# LEDdriverSFE_CREE.net
KiCad netlist of a schematic drawn in EAGLE
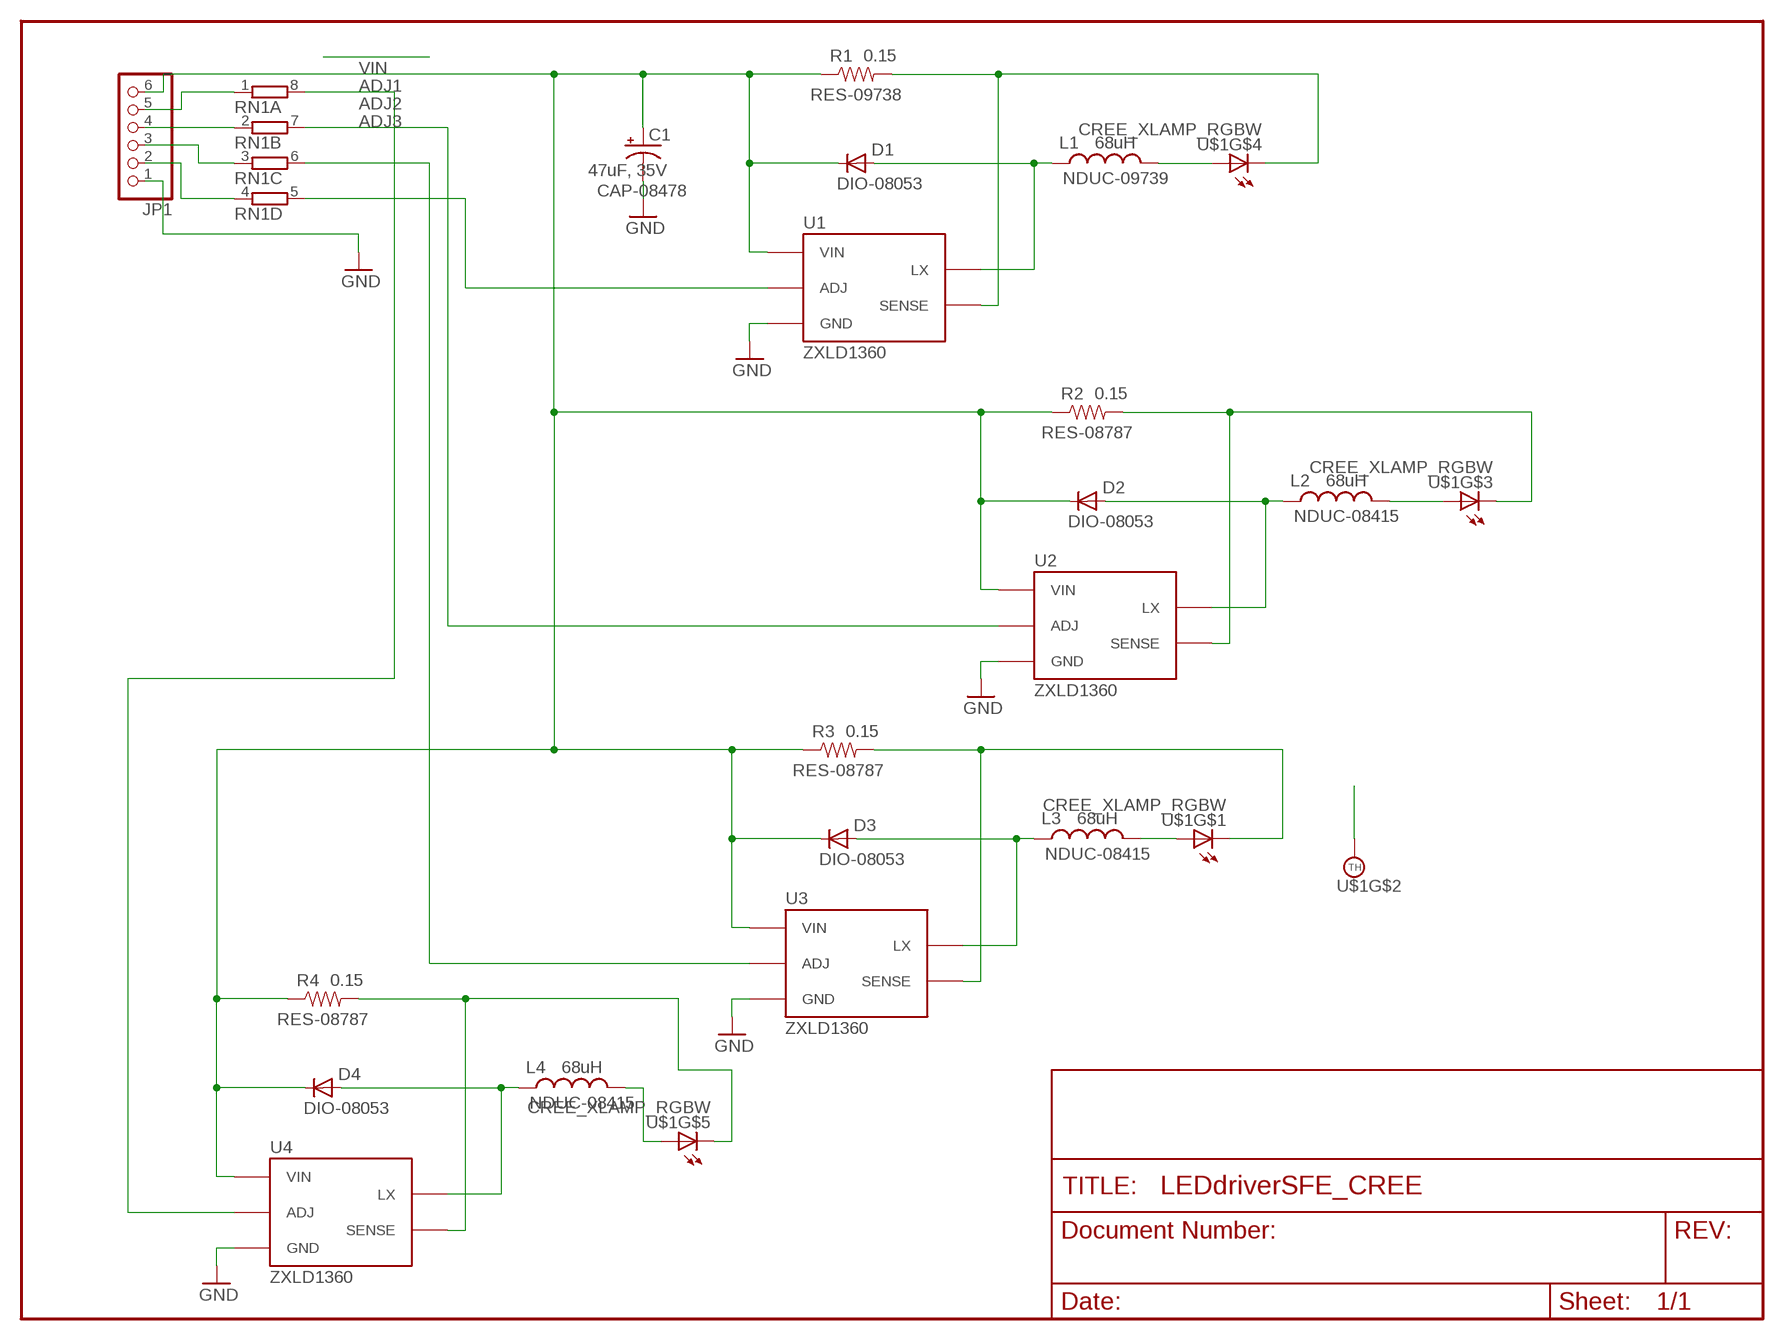
[diagram p0: schematic, sheet 1]

(export (version "E")
  (design (tool "Eeschema 10.0.6"))
  (components
    (comp (ref "C1")
      (value "47uF, 35V")
      (footprint "eagle-import:PANASONIC_D")
      (libsource (lib "eagle-import") (part "CAP_POLD"))
    )
    (comp (ref "D1")
      (value "MBRA140")
      (footprint "eagle-import:SMA-DIODE")
      (libsource (lib "eagle-import") (part "DIODESMA"))
    )
    (comp (ref "D2")
      (value "MBRA140")
      (footprint "eagle-import:SMA-DIODE")
      (libsource (lib "eagle-import") (part "DIODESMA"))
    )
    (comp (ref "D3")
      (value "MBRA140")
      (footprint "eagle-import:SMA-DIODE")
      (libsource (lib "eagle-import") (part "DIODESMA"))
    )
    (comp (ref "D4")
      (value "MBRA140")
      (footprint "eagle-import:SMA-DIODE")
      (libsource (lib "eagle-import") (part "DIODESMA"))
    )
    (comp (ref "JP1")
      (value "PINHD-1X6")
      (footprint "eagle-import:1X06")
      (libsource (lib "eagle-import") (part "PINHD-1X6"))
    )
    (comp (ref "L1")
      (value "68uH")
      (footprint "eagle-import:CR75")
      (libsource (lib "eagle-import") (part "INDUCTORCR75"))
    )
    (comp (ref "L2")
      (value "68uH")
      (footprint "eagle-import:CR75")
      (libsource (lib "eagle-import") (part "INDUCTORCR75"))
    )
    (comp (ref "L3")
      (value "68uH")
      (footprint "eagle-import:CR75")
      (libsource (lib "eagle-import") (part "INDUCTORCR75"))
    )
    (comp (ref "L4")
      (value "68uH")
      (footprint "eagle-import:CR75")
      (libsource (lib "eagle-import") (part "INDUCTORCR75"))
    )
    (comp (ref "R1")
      (value "0.15")
      (footprint "eagle-import:0603-RES")
      (libsource (lib "eagle-import") (part "RESISTOR0603-RES"))
    )
    (comp (ref "R2")
      (value "0.15")
      (footprint "eagle-import:0603-RES")
      (libsource (lib "eagle-import") (part "RESISTOR0603-RES"))
    )
    (comp (ref "R3")
      (value "0.15")
      (footprint "eagle-import:0603-RES")
      (libsource (lib "eagle-import") (part "RESISTOR0603-RES"))
    )
    (comp (ref "R4")
      (value "0.15")
      (footprint "eagle-import:0603-RES")
      (libsource (lib "eagle-import") (part "RESISTOR0603-RES"))
    )
    (comp (ref "RN1")
      (value "4R-NEXBV8V")
      (footprint "eagle-import:EXBV8V")
      (libsource (lib "eagle-import") (part "4R-NEXBV8V"))
    )
    (comp (ref "U$1")
      (value "CREE_XLAMP_RGBW")
      (footprint "eagle-import:CREE_XLAMP_XML")
      (libsource (lib "eagle-import") (part "CREE_XLAMP_RGBW"))
    )
    (comp (ref "U1")
      (value "ZXLD1360")
      (footprint "eagle-import:SOT23-5")
      (libsource (lib "eagle-import") (part "ZXLD1360"))
    )
    (comp (ref "U2")
      (value "ZXLD1360")
      (footprint "eagle-import:SOT23-5")
      (libsource (lib "eagle-import") (part "ZXLD1360"))
    )
    (comp (ref "U3")
      (value "ZXLD1360")
      (footprint "eagle-import:SOT23-5")
      (libsource (lib "eagle-import") (part "ZXLD1360"))
    )
    (comp (ref "U4")
      (value "ZXLD1360")
      (footprint "eagle-import:SOT23-5")
      (libsource (lib "eagle-import") (part "ZXLD1360"))
    )
  )
  (nets
    (net (code "1") (name "/ADJ1") (class "Default")
      (node (ref "RN1") (pin "5") (pinfunction "2_5") (pintype "passive"))
      (node (ref "U1") (pin "3") (pinfunction "ADJ_3") (pintype "bidirectional"))
    )
    (net (code "2") (name "/ADJ2") (class "Default")
      (node (ref "RN1") (pin "7") (pinfunction "2_7") (pintype "passive"))
      (node (ref "U2") (pin "3") (pinfunction "ADJ_3") (pintype "bidirectional"))
    )
    (net (code "3") (name "/ADJ3") (class "Default")
      (node (ref "RN1") (pin "6") (pinfunction "2_6") (pintype "passive"))
      (node (ref "U3") (pin "3") (pinfunction "ADJ_3") (pintype "bidirectional"))
    )
    (net (code "4") (name "/VIN") (class "Default")
      (node (ref "C1") (pin "+") (pinfunction "+_+") (pintype "passive"))
      (node (ref "D1") (pin "C") (pinfunction "C_C") (pintype "passive"))
      (node (ref "D2") (pin "C") (pinfunction "C_C") (pintype "passive"))
      (node (ref "D3") (pin "C") (pinfunction "C_C") (pintype "passive"))
      (node (ref "D4") (pin "C") (pinfunction "C_C") (pintype "passive"))
      (node (ref "JP1") (pin "6") (pinfunction "6_6") (pintype "passive"))
      (node (ref "R1") (pin "1") (pinfunction "1_1") (pintype "passive"))
      (node (ref "R2") (pin "1") (pinfunction "1_1") (pintype "passive"))
      (node (ref "R3") (pin "1") (pinfunction "1_1") (pintype "passive"))
      (node (ref "R4") (pin "1") (pinfunction "1_1") (pintype "passive"))
      (node (ref "U1") (pin "5") (pinfunction "VIN_5") (pintype "bidirectional"))
      (node (ref "U2") (pin "5") (pinfunction "VIN_5") (pintype "bidirectional"))
      (node (ref "U3") (pin "5") (pinfunction "VIN_5") (pintype "bidirectional"))
      (node (ref "U4") (pin "5") (pinfunction "VIN_5") (pintype "bidirectional"))
    )
    (net (code "5") (name "GND") (class "Default")
      (node (ref "C1") (pin "-") (pinfunction "-_-") (pintype "passive"))
      (node (ref "JP1") (pin "1") (pinfunction "1_1") (pintype "passive"))
      (node (ref "U1") (pin "2") (pinfunction "GND_2") (pintype "bidirectional"))
      (node (ref "U2") (pin "2") (pinfunction "GND_2") (pintype "bidirectional"))
      (node (ref "U3") (pin "2") (pinfunction "GND_2") (pintype "bidirectional"))
      (node (ref "U4") (pin "2") (pinfunction "GND_2") (pintype "bidirectional"))
    )
    (net (code "6") (name "Net-(JP1-Pad5)") (class "Default")
      (node (ref "JP1") (pin "5") (pinfunction "5_5") (pintype "passive"))
      (node (ref "RN1") (pin "1") (pinfunction "1_1") (pintype "passive"))
    )
    (net (code "7") (name "Net-(L1-1)") (class "Default")
      (node (ref "D1") (pin "A") (pinfunction "A_A") (pintype "passive"))
      (node (ref "L1") (pin "P$1") (pinfunction "1_P$1") (pintype "passive"))
      (node (ref "U1") (pin "1") (pinfunction "LX_1") (pintype "bidirectional"))
    )
    (net (code "8") (name "Net-(L1-2)") (class "Default")
      (node (ref "L1") (pin "P$2") (pinfunction "2_P$2") (pintype "passive"))
      (node (ref "U$1") (pin "3") (pinfunction "A_3") (pintype "passive"))
    )
    (net (code "9") (name "Net-(L2-1)") (class "Default")
      (node (ref "D2") (pin "A") (pinfunction "A_A") (pintype "passive"))
      (node (ref "L2") (pin "P$1") (pinfunction "1_P$1") (pintype "passive"))
      (node (ref "U2") (pin "1") (pinfunction "LX_1") (pintype "bidirectional"))
    )
    (net (code "10") (name "Net-(L2-2)") (class "Default")
      (node (ref "L2") (pin "P$2") (pinfunction "2_P$2") (pintype "passive"))
      (node (ref "U$1") (pin "2") (pinfunction "A_2") (pintype "passive"))
    )
    (net (code "11") (name "Net-(L3-1)") (class "Default")
      (node (ref "D3") (pin "A") (pinfunction "A_A") (pintype "passive"))
      (node (ref "L3") (pin "P$1") (pinfunction "1_P$1") (pintype "passive"))
      (node (ref "U3") (pin "1") (pinfunction "LX_1") (pintype "bidirectional"))
    )
    (net (code "12") (name "Net-(L3-2)") (class "Default")
      (node (ref "L3") (pin "P$2") (pinfunction "2_P$2") (pintype "passive"))
      (node (ref "U$1") (pin "1") (pinfunction "A_1") (pintype "passive"))
    )
    (net (code "13") (name "Net-(L4-1)") (class "Default")
      (node (ref "D4") (pin "A") (pinfunction "A_A") (pintype "passive"))
      (node (ref "L4") (pin "P$1") (pinfunction "1_P$1") (pintype "passive"))
      (node (ref "U4") (pin "1") (pinfunction "LX_1") (pintype "bidirectional"))
    )
    (net (code "14") (name "Net-(L4-2)") (class "Default")
      (node (ref "L4") (pin "P$2") (pinfunction "2_P$2") (pintype "passive"))
      (node (ref "U$1") (pin "4") (pinfunction "A_4") (pintype "passive"))
    )
    (net (code "15") (name "Net-(RN1A-2)") (class "Default")
      (node (ref "RN1") (pin "8") (pinfunction "2_8") (pintype "passive"))
      (node (ref "U4") (pin "3") (pinfunction "ADJ_3") (pintype "bidirectional"))
    )
    (net (code "16") (name "Net-(RN1B-1)") (class "Default")
      (node (ref "JP1") (pin "4") (pinfunction "4_4") (pintype "passive"))
      (node (ref "RN1") (pin "2") (pinfunction "1_2") (pintype "passive"))
    )
    (net (code "17") (name "Net-(RN1C-1)") (class "Default")
      (node (ref "JP1") (pin "3") (pinfunction "3_3") (pintype "passive"))
      (node (ref "RN1") (pin "3") (pinfunction "1_3") (pintype "passive"))
    )
    (net (code "18") (name "Net-(RN1D-1)") (class "Default")
      (node (ref "JP1") (pin "2") (pinfunction "2_2") (pintype "passive"))
      (node (ref "RN1") (pin "4") (pinfunction "1_4") (pintype "passive"))
    )
    (net (code "19") (name "Net-(U$1A-C)") (class "Default")
      (node (ref "R3") (pin "2") (pinfunction "2_2") (pintype "passive"))
      (node (ref "U$1") (pin "8") (pinfunction "C_8") (pintype "passive"))
      (node (ref "U3") (pin "4") (pinfunction "SENSE_4") (pintype "bidirectional"))
    )
    (net (code "20") (name "Net-(U$1C-C)") (class "Default")
      (node (ref "R2") (pin "2") (pinfunction "2_2") (pintype "passive"))
      (node (ref "U$1") (pin "7") (pinfunction "C_7") (pintype "passive"))
      (node (ref "U2") (pin "4") (pinfunction "SENSE_4") (pintype "bidirectional"))
    )
    (net (code "21") (name "Net-(U$1D-C)") (class "Default")
      (node (ref "R1") (pin "2") (pinfunction "2_2") (pintype "passive"))
      (node (ref "U$1") (pin "6") (pinfunction "C_6") (pintype "passive"))
      (node (ref "U1") (pin "4") (pinfunction "SENSE_4") (pintype "bidirectional"))
    )
    (net (code "22") (name "Net-(U$1E-C)") (class "Default")
      (node (ref "R4") (pin "2") (pinfunction "2_2") (pintype "passive"))
      (node (ref "U$1") (pin "5") (pinfunction "C_5") (pintype "passive"))
      (node (ref "U4") (pin "4") (pinfunction "SENSE_4") (pintype "bidirectional"))
    )
    (net (code "23") (name "unconnected-(U$1B-TH-PadP$1)") (class "Default")
      (node (ref "U$1") (pin "P$1") (pinfunction "TH_P$1") (pintype "passive"))
    )
  )
)
